# LED_board.net
KiCad netlist of a schematic drawn in EAGLE
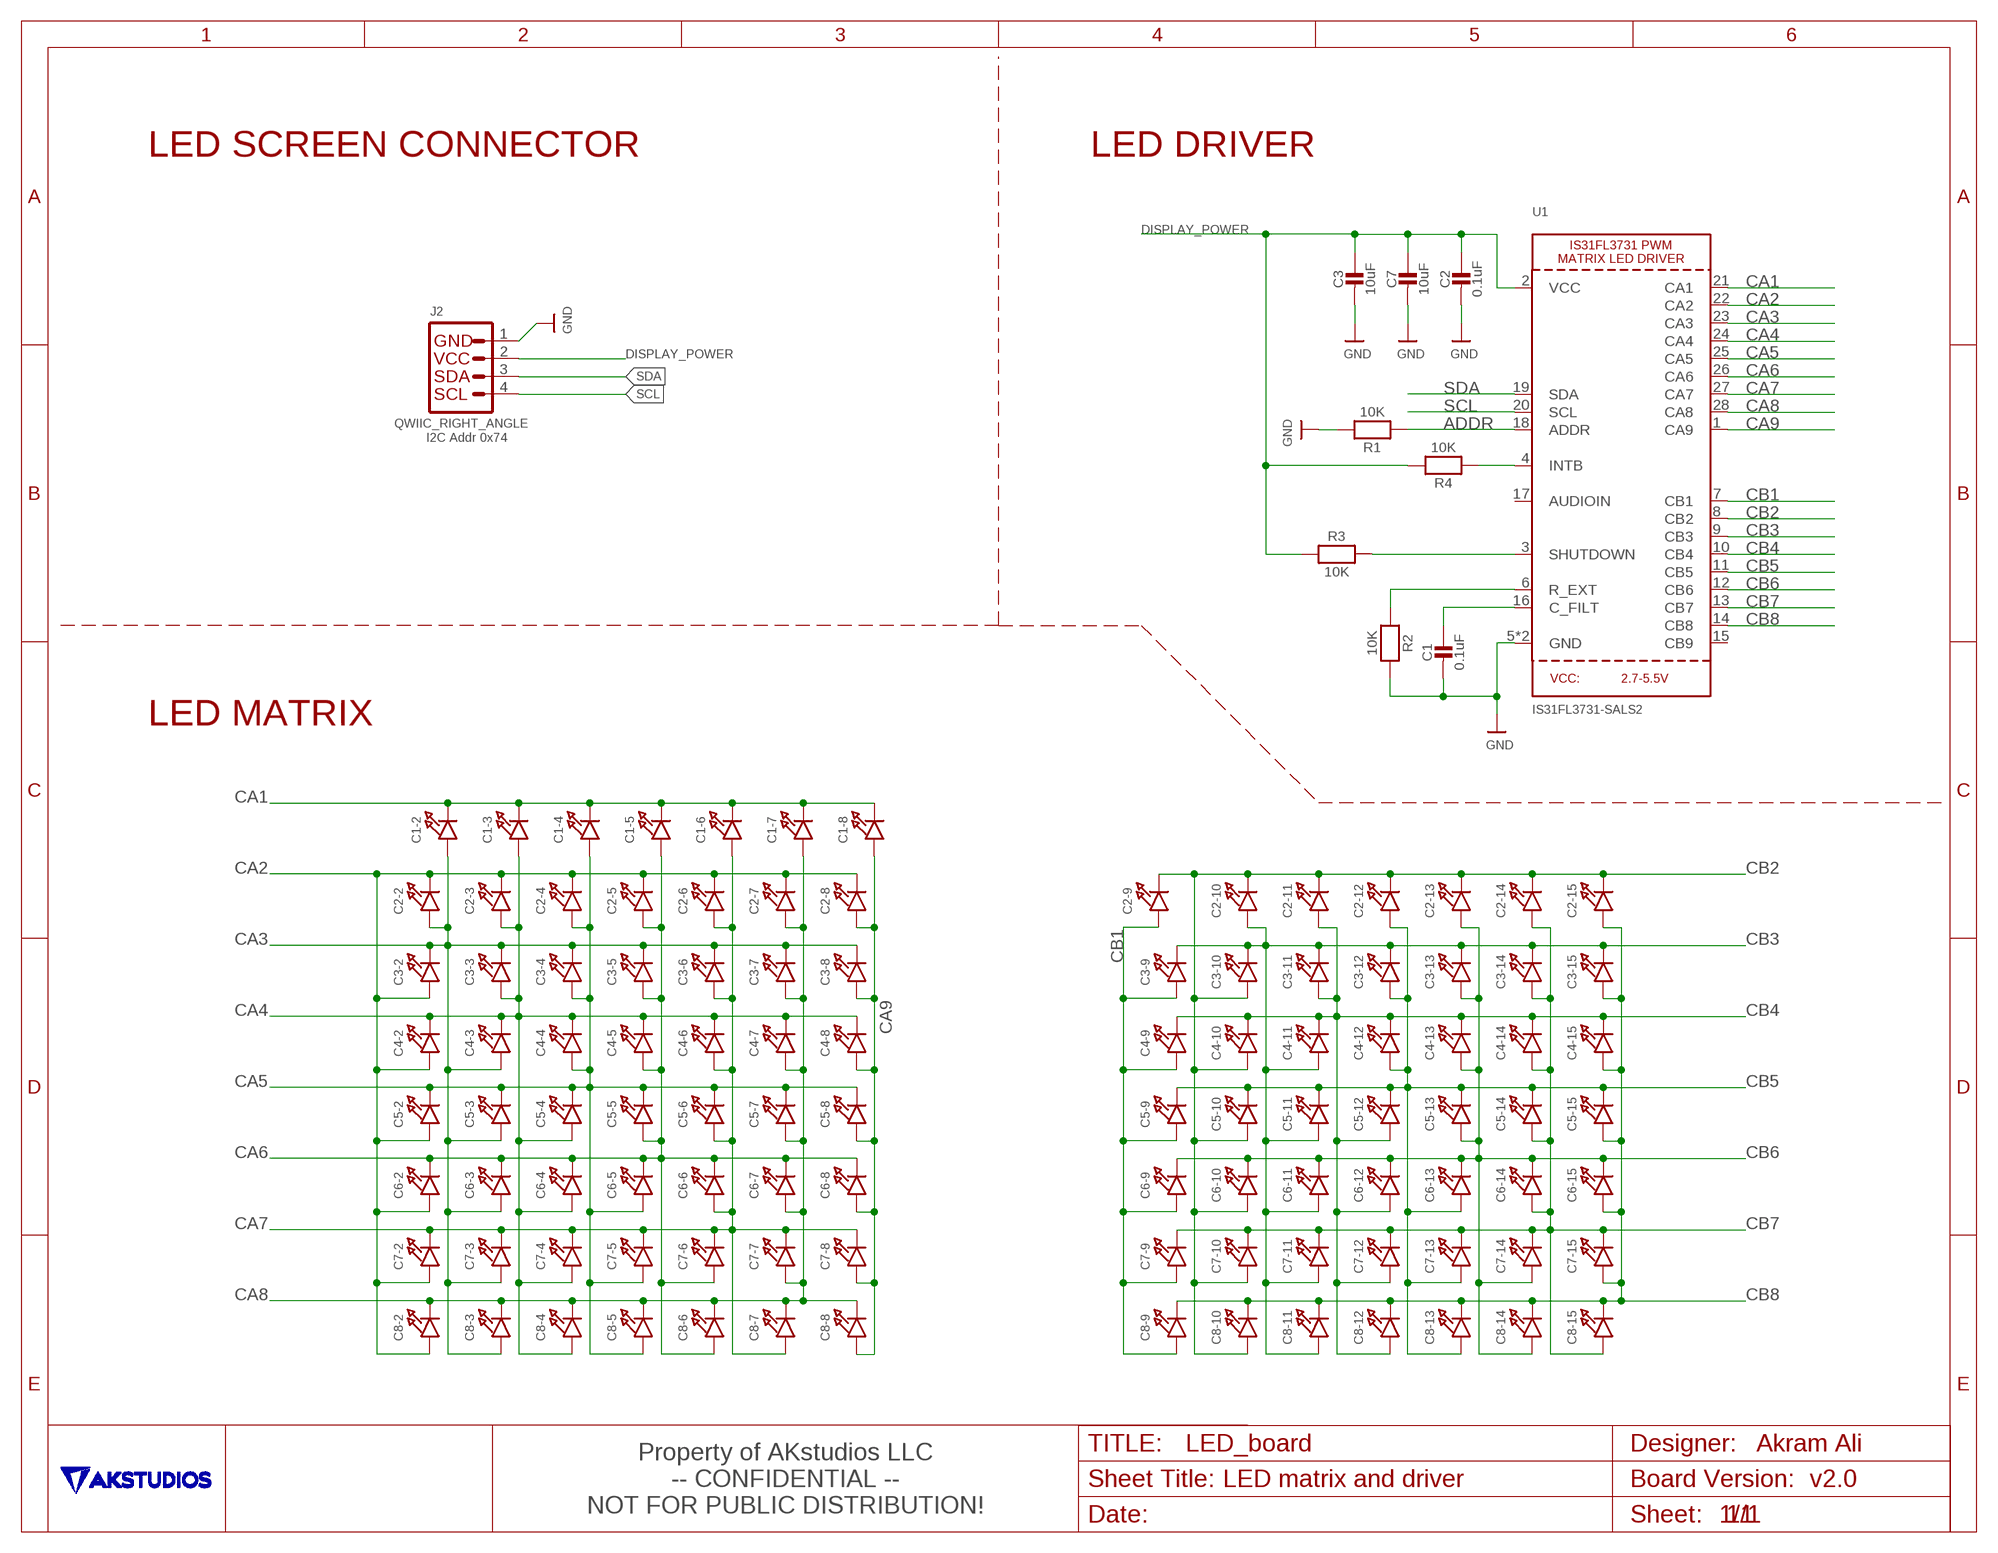
[diagram p0: schematic, sheet 1]

(export (version "E")
  (design (tool "Eeschema 10.0.6"))
  (components
    (comp (ref "C1")
      (value "0.1uF")
      (footprint "eagle-import:MICROBUILDER__0402MP")
      (fields (field (name "MPN") "GRM155R71C104KA88J"))
      (libsource (lib "eagle-import") (part "MICROBUILDER_CAP_CERAMIC_0402MP"))
    )
    (comp (ref "C1-2")
      (value "LED0603_NOOUTLINE")
      (footprint "eagle-import:CHIPLED_0603_NOOUTLINE")
      (libsource (lib "eagle-import") (part "LED0603_NOOUTLINE"))
    )
    (comp (ref "C1-3")
      (value "LED0603_NOOUTLINE")
      (footprint "eagle-import:CHIPLED_0603_NOOUTLINE")
      (libsource (lib "eagle-import") (part "LED0603_NOOUTLINE"))
    )
    (comp (ref "C1-4")
      (value "LED0603_NOOUTLINE")
      (footprint "eagle-import:CHIPLED_0603_NOOUTLINE")
      (libsource (lib "eagle-import") (part "LED0603_NOOUTLINE"))
    )
    (comp (ref "C1-5")
      (value "LED0603_NOOUTLINE")
      (footprint "eagle-import:CHIPLED_0603_NOOUTLINE")
      (libsource (lib "eagle-import") (part "LED0603_NOOUTLINE"))
    )
    (comp (ref "C1-6")
      (value "LED0603_NOOUTLINE")
      (footprint "eagle-import:CHIPLED_0603_NOOUTLINE")
      (libsource (lib "eagle-import") (part "LED0603_NOOUTLINE"))
    )
    (comp (ref "C1-7")
      (value "LED0603_NOOUTLINE")
      (footprint "eagle-import:CHIPLED_0603_NOOUTLINE")
      (libsource (lib "eagle-import") (part "LED0603_NOOUTLINE"))
    )
    (comp (ref "C1-8")
      (value "LED0603_NOOUTLINE")
      (footprint "eagle-import:CHIPLED_0603_NOOUTLINE")
      (libsource (lib "eagle-import") (part "LED0603_NOOUTLINE"))
    )
    (comp (ref "C2")
      (value "0.1uF")
      (footprint "eagle-import:MICROBUILDER__0402MP")
      (fields (field (name "MPN") "GRM155R71C104KA88J"))
      (libsource (lib "eagle-import") (part "MICROBUILDER_CAP_CERAMIC_0402MP"))
    )
    (comp (ref "C2-2")
      (value "LED0603_NOOUTLINE")
      (footprint "eagle-import:CHIPLED_0603_NOOUTLINE")
      (libsource (lib "eagle-import") (part "LED0603_NOOUTLINE"))
    )
    (comp (ref "C2-3")
      (value "LED0603_NOOUTLINE")
      (footprint "eagle-import:CHIPLED_0603_NOOUTLINE")
      (libsource (lib "eagle-import") (part "LED0603_NOOUTLINE"))
    )
    (comp (ref "C2-4")
      (value "LED0603_NOOUTLINE")
      (footprint "eagle-import:CHIPLED_0603_NOOUTLINE")
      (libsource (lib "eagle-import") (part "LED0603_NOOUTLINE"))
    )
    (comp (ref "C2-5")
      (value "LED0603_NOOUTLINE")
      (footprint "eagle-import:CHIPLED_0603_NOOUTLINE")
      (libsource (lib "eagle-import") (part "LED0603_NOOUTLINE"))
    )
    (comp (ref "C2-6")
      (value "LED0603_NOOUTLINE")
      (footprint "eagle-import:CHIPLED_0603_NOOUTLINE")
      (libsource (lib "eagle-import") (part "LED0603_NOOUTLINE"))
    )
    (comp (ref "C2-7")
      (value "LED0603_NOOUTLINE")
      (footprint "eagle-import:CHIPLED_0603_NOOUTLINE")
      (libsource (lib "eagle-import") (part "LED0603_NOOUTLINE"))
    )
    (comp (ref "C2-8")
      (value "LED0603_NOOUTLINE")
      (footprint "eagle-import:CHIPLED_0603_NOOUTLINE")
      (libsource (lib "eagle-import") (part "LED0603_NOOUTLINE"))
    )
    (comp (ref "C2-9")
      (value "LED0603_NOOUTLINE")
      (footprint "eagle-import:CHIPLED_0603_NOOUTLINE")
      (libsource (lib "eagle-import") (part "LED0603_NOOUTLINE"))
    )
    (comp (ref "C2-10")
      (value "LED0603_NOOUTLINE")
      (footprint "eagle-import:CHIPLED_0603_NOOUTLINE")
      (libsource (lib "eagle-import") (part "LED0603_NOOUTLINE"))
    )
    (comp (ref "C2-11")
      (value "LED0603_NOOUTLINE")
      (footprint "eagle-import:CHIPLED_0603_NOOUTLINE")
      (libsource (lib "eagle-import") (part "LED0603_NOOUTLINE"))
    )
    (comp (ref "C2-12")
      (value "LED0603_NOOUTLINE")
      (footprint "eagle-import:CHIPLED_0603_NOOUTLINE")
      (libsource (lib "eagle-import") (part "LED0603_NOOUTLINE"))
    )
    (comp (ref "C2-13")
      (value "LED0603_NOOUTLINE")
      (footprint "eagle-import:CHIPLED_0603_NOOUTLINE")
      (libsource (lib "eagle-import") (part "LED0603_NOOUTLINE"))
    )
    (comp (ref "C2-14")
      (value "LED0603_NOOUTLINE")
      (footprint "eagle-import:CHIPLED_0603_NOOUTLINE")
      (libsource (lib "eagle-import") (part "LED0603_NOOUTLINE"))
    )
    (comp (ref "C2-15")
      (value "LED0603_NOOUTLINE")
      (footprint "eagle-import:CHIPLED_0603_NOOUTLINE")
      (libsource (lib "eagle-import") (part "LED0603_NOOUTLINE"))
    )
    (comp (ref "C3")
      (value "10uF")
      (footprint "eagle-import:MICROBUILDER__0402MP")
      (fields (field (name "MPN") "GRM155R71C104KA88J"))
      (libsource (lib "eagle-import") (part "MICROBUILDER_CAP_CERAMIC_0402MP"))
    )
    (comp (ref "C3-2")
      (value "LED0603_NOOUTLINE")
      (footprint "eagle-import:CHIPLED_0603_NOOUTLINE")
      (libsource (lib "eagle-import") (part "LED0603_NOOUTLINE"))
    )
    (comp (ref "C3-3")
      (value "LED0603_NOOUTLINE")
      (footprint "eagle-import:CHIPLED_0603_NOOUTLINE")
      (libsource (lib "eagle-import") (part "LED0603_NOOUTLINE"))
    )
    (comp (ref "C3-4")
      (value "LED0603_NOOUTLINE")
      (footprint "eagle-import:CHIPLED_0603_NOOUTLINE")
      (libsource (lib "eagle-import") (part "LED0603_NOOUTLINE"))
    )
    (comp (ref "C3-5")
      (value "LED0603_NOOUTLINE")
      (footprint "eagle-import:CHIPLED_0603_NOOUTLINE")
      (libsource (lib "eagle-import") (part "LED0603_NOOUTLINE"))
    )
    (comp (ref "C3-6")
      (value "LED0603_NOOUTLINE")
      (footprint "eagle-import:CHIPLED_0603_NOOUTLINE")
      (libsource (lib "eagle-import") (part "LED0603_NOOUTLINE"))
    )
    (comp (ref "C3-7")
      (value "LED0603_NOOUTLINE")
      (footprint "eagle-import:CHIPLED_0603_NOOUTLINE")
      (libsource (lib "eagle-import") (part "LED0603_NOOUTLINE"))
    )
    (comp (ref "C3-8")
      (value "LED0603_NOOUTLINE")
      (footprint "eagle-import:CHIPLED_0603_NOOUTLINE")
      (libsource (lib "eagle-import") (part "LED0603_NOOUTLINE"))
    )
    (comp (ref "C3-9")
      (value "LED0603_NOOUTLINE")
      (footprint "eagle-import:CHIPLED_0603_NOOUTLINE")
      (libsource (lib "eagle-import") (part "LED0603_NOOUTLINE"))
    )
    (comp (ref "C3-10")
      (value "LED0603_NOOUTLINE")
      (footprint "eagle-import:CHIPLED_0603_NOOUTLINE")
      (libsource (lib "eagle-import") (part "LED0603_NOOUTLINE"))
    )
    (comp (ref "C3-11")
      (value "LED0603_NOOUTLINE")
      (footprint "eagle-import:CHIPLED_0603_NOOUTLINE")
      (libsource (lib "eagle-import") (part "LED0603_NOOUTLINE"))
    )
    (comp (ref "C3-12")
      (value "LED0603_NOOUTLINE")
      (footprint "eagle-import:CHIPLED_0603_NOOUTLINE")
      (libsource (lib "eagle-import") (part "LED0603_NOOUTLINE"))
    )
    (comp (ref "C3-13")
      (value "LED0603_NOOUTLINE")
      (footprint "eagle-import:CHIPLED_0603_NOOUTLINE")
      (libsource (lib "eagle-import") (part "LED0603_NOOUTLINE"))
    )
    (comp (ref "C3-14")
      (value "LED0603_NOOUTLINE")
      (footprint "eagle-import:CHIPLED_0603_NOOUTLINE")
      (libsource (lib "eagle-import") (part "LED0603_NOOUTLINE"))
    )
    (comp (ref "C3-15")
      (value "LED0603_NOOUTLINE")
      (footprint "eagle-import:CHIPLED_0603_NOOUTLINE")
      (libsource (lib "eagle-import") (part "LED0603_NOOUTLINE"))
    )
    (comp (ref "C4-2")
      (value "LED0603_NOOUTLINE")
      (footprint "eagle-import:CHIPLED_0603_NOOUTLINE")
      (libsource (lib "eagle-import") (part "LED0603_NOOUTLINE"))
    )
    (comp (ref "C4-3")
      (value "LED0603_NOOUTLINE")
      (footprint "eagle-import:CHIPLED_0603_NOOUTLINE")
      (libsource (lib "eagle-import") (part "LED0603_NOOUTLINE"))
    )
    (comp (ref "C4-4")
      (value "LED0603_NOOUTLINE")
      (footprint "eagle-import:CHIPLED_0603_NOOUTLINE")
      (libsource (lib "eagle-import") (part "LED0603_NOOUTLINE"))
    )
    (comp (ref "C4-5")
      (value "LED0603_NOOUTLINE")
      (footprint "eagle-import:CHIPLED_0603_NOOUTLINE")
      (libsource (lib "eagle-import") (part "LED0603_NOOUTLINE"))
    )
    (comp (ref "C4-6")
      (value "LED0603_NOOUTLINE")
      (footprint "eagle-import:CHIPLED_0603_NOOUTLINE")
      (libsource (lib "eagle-import") (part "LED0603_NOOUTLINE"))
    )
    (comp (ref "C4-7")
      (value "LED0603_NOOUTLINE")
      (footprint "eagle-import:CHIPLED_0603_NOOUTLINE")
      (libsource (lib "eagle-import") (part "LED0603_NOOUTLINE"))
    )
    (comp (ref "C4-8")
      (value "LED0603_NOOUTLINE")
      (footprint "eagle-import:CHIPLED_0603_NOOUTLINE")
      (libsource (lib "eagle-import") (part "LED0603_NOOUTLINE"))
    )
    (comp (ref "C4-9")
      (value "LED0603_NOOUTLINE")
      (footprint "eagle-import:CHIPLED_0603_NOOUTLINE")
      (libsource (lib "eagle-import") (part "LED0603_NOOUTLINE"))
    )
    (comp (ref "C4-10")
      (value "LED0603_NOOUTLINE")
      (footprint "eagle-import:CHIPLED_0603_NOOUTLINE")
      (libsource (lib "eagle-import") (part "LED0603_NOOUTLINE"))
    )
    (comp (ref "C4-11")
      (value "LED0603_NOOUTLINE")
      (footprint "eagle-import:CHIPLED_0603_NOOUTLINE")
      (libsource (lib "eagle-import") (part "LED0603_NOOUTLINE"))
    )
    (comp (ref "C4-12")
      (value "LED0603_NOOUTLINE")
      (footprint "eagle-import:CHIPLED_0603_NOOUTLINE")
      (libsource (lib "eagle-import") (part "LED0603_NOOUTLINE"))
    )
    (comp (ref "C4-13")
      (value "LED0603_NOOUTLINE")
      (footprint "eagle-import:CHIPLED_0603_NOOUTLINE")
      (libsource (lib "eagle-import") (part "LED0603_NOOUTLINE"))
    )
    (comp (ref "C4-14")
      (value "LED0603_NOOUTLINE")
      (footprint "eagle-import:CHIPLED_0603_NOOUTLINE")
      (libsource (lib "eagle-import") (part "LED0603_NOOUTLINE"))
    )
    (comp (ref "C4-15")
      (value "LED0603_NOOUTLINE")
      (footprint "eagle-import:CHIPLED_0603_NOOUTLINE")
      (libsource (lib "eagle-import") (part "LED0603_NOOUTLINE"))
    )
    (comp (ref "C5-2")
      (value "LED0603_NOOUTLINE")
      (footprint "eagle-import:CHIPLED_0603_NOOUTLINE")
      (libsource (lib "eagle-import") (part "LED0603_NOOUTLINE"))
    )
    (comp (ref "C5-3")
      (value "LED0603_NOOUTLINE")
      (footprint "eagle-import:CHIPLED_0603_NOOUTLINE")
      (libsource (lib "eagle-import") (part "LED0603_NOOUTLINE"))
    )
    (comp (ref "C5-4")
      (value "LED0603_NOOUTLINE")
      (footprint "eagle-import:CHIPLED_0603_NOOUTLINE")
      (libsource (lib "eagle-import") (part "LED0603_NOOUTLINE"))
    )
    (comp (ref "C5-5")
      (value "LED0603_NOOUTLINE")
      (footprint "eagle-import:CHIPLED_0603_NOOUTLINE")
      (libsource (lib "eagle-import") (part "LED0603_NOOUTLINE"))
    )
    (comp (ref "C5-6")
      (value "LED0603_NOOUTLINE")
      (footprint "eagle-import:CHIPLED_0603_NOOUTLINE")
      (libsource (lib "eagle-import") (part "LED0603_NOOUTLINE"))
    )
    (comp (ref "C5-7")
      (value "LED0603_NOOUTLINE")
      (footprint "eagle-import:CHIPLED_0603_NOOUTLINE")
      (libsource (lib "eagle-import") (part "LED0603_NOOUTLINE"))
    )
    (comp (ref "C5-8")
      (value "LED0603_NOOUTLINE")
      (footprint "eagle-import:CHIPLED_0603_NOOUTLINE")
      (libsource (lib "eagle-import") (part "LED0603_NOOUTLINE"))
    )
    (comp (ref "C5-9")
      (value "LED0603_NOOUTLINE")
      (footprint "eagle-import:CHIPLED_0603_NOOUTLINE")
      (libsource (lib "eagle-import") (part "LED0603_NOOUTLINE"))
    )
    (comp (ref "C5-10")
      (value "LED0603_NOOUTLINE")
      (footprint "eagle-import:CHIPLED_0603_NOOUTLINE")
      (libsource (lib "eagle-import") (part "LED0603_NOOUTLINE"))
    )
    (comp (ref "C5-11")
      (value "LED0603_NOOUTLINE")
      (footprint "eagle-import:CHIPLED_0603_NOOUTLINE")
      (libsource (lib "eagle-import") (part "LED0603_NOOUTLINE"))
    )
    (comp (ref "C5-12")
      (value "LED0603_NOOUTLINE")
      (footprint "eagle-import:CHIPLED_0603_NOOUTLINE")
      (libsource (lib "eagle-import") (part "LED0603_NOOUTLINE"))
    )
    (comp (ref "C5-13")
      (value "LED0603_NOOUTLINE")
      (footprint "eagle-import:CHIPLED_0603_NOOUTLINE")
      (libsource (lib "eagle-import") (part "LED0603_NOOUTLINE"))
    )
    (comp (ref "C5-14")
      (value "LED0603_NOOUTLINE")
      (footprint "eagle-import:CHIPLED_0603_NOOUTLINE")
      (libsource (lib "eagle-import") (part "LED0603_NOOUTLINE"))
    )
    (comp (ref "C5-15")
      (value "LED0603_NOOUTLINE")
      (footprint "eagle-import:CHIPLED_0603_NOOUTLINE")
      (libsource (lib "eagle-import") (part "LED0603_NOOUTLINE"))
    )
    (comp (ref "C6-2")
      (value "LED0603_NOOUTLINE")
      (footprint "eagle-import:CHIPLED_0603_NOOUTLINE")
      (libsource (lib "eagle-import") (part "LED0603_NOOUTLINE"))
    )
    (comp (ref "C6-3")
      (value "LED0603_NOOUTLINE")
      (footprint "eagle-import:CHIPLED_0603_NOOUTLINE")
      (libsource (lib "eagle-import") (part "LED0603_NOOUTLINE"))
    )
    (comp (ref "C6-4")
      (value "LED0603_NOOUTLINE")
      (footprint "eagle-import:CHIPLED_0603_NOOUTLINE")
      (libsource (lib "eagle-import") (part "LED0603_NOOUTLINE"))
    )
    (comp (ref "C6-5")
      (value "LED0603_NOOUTLINE")
      (footprint "eagle-import:CHIPLED_0603_NOOUTLINE")
      (libsource (lib "eagle-import") (part "LED0603_NOOUTLINE"))
    )
    (comp (ref "C6-6")
      (value "LED0603_NOOUTLINE")
      (footprint "eagle-import:CHIPLED_0603_NOOUTLINE")
      (libsource (lib "eagle-import") (part "LED0603_NOOUTLINE"))
    )
    (comp (ref "C6-7")
      (value "LED0603_NOOUTLINE")
      (footprint "eagle-import:CHIPLED_0603_NOOUTLINE")
      (libsource (lib "eagle-import") (part "LED0603_NOOUTLINE"))
    )
    (comp (ref "C6-8")
      (value "LED0603_NOOUTLINE")
      (footprint "eagle-import:CHIPLED_0603_NOOUTLINE")
      (libsource (lib "eagle-import") (part "LED0603_NOOUTLINE"))
    )
    (comp (ref "C6-9")
      (value "LED0603_NOOUTLINE")
      (footprint "eagle-import:CHIPLED_0603_NOOUTLINE")
      (libsource (lib "eagle-import") (part "LED0603_NOOUTLINE"))
    )
    (comp (ref "C6-10")
      (value "LED0603_NOOUTLINE")
      (footprint "eagle-import:CHIPLED_0603_NOOUTLINE")
      (libsource (lib "eagle-import") (part "LED0603_NOOUTLINE"))
    )
    (comp (ref "C6-11")
      (value "LED0603_NOOUTLINE")
      (footprint "eagle-import:CHIPLED_0603_NOOUTLINE")
      (libsource (lib "eagle-import") (part "LED0603_NOOUTLINE"))
    )
    (comp (ref "C6-12")
      (value "LED0603_NOOUTLINE")
      (footprint "eagle-import:CHIPLED_0603_NOOUTLINE")
      (libsource (lib "eagle-import") (part "LED0603_NOOUTLINE"))
    )
    (comp (ref "C6-13")
      (value "LED0603_NOOUTLINE")
      (footprint "eagle-import:CHIPLED_0603_NOOUTLINE")
      (libsource (lib "eagle-import") (part "LED0603_NOOUTLINE"))
    )
    (comp (ref "C6-14")
      (value "LED0603_NOOUTLINE")
      (footprint "eagle-import:CHIPLED_0603_NOOUTLINE")
      (libsource (lib "eagle-import") (part "LED0603_NOOUTLINE"))
    )
    (comp (ref "C6-15")
      (value "LED0603_NOOUTLINE")
      (footprint "eagle-import:CHIPLED_0603_NOOUTLINE")
      (libsource (lib "eagle-import") (part "LED0603_NOOUTLINE"))
    )
    (comp (ref "C7")
      (value "10uF")
      (footprint "eagle-import:MICROBUILDER__0402MP")
      (fields (field (name "MPN") "GRM155R71C104KA88J"))
      (libsource (lib "eagle-import") (part "MICROBUILDER_CAP_CERAMIC_0402MP"))
    )
    (comp (ref "C7-2")
      (value "LED0603_NOOUTLINE")
      (footprint "eagle-import:CHIPLED_0603_NOOUTLINE")
      (libsource (lib "eagle-import") (part "LED0603_NOOUTLINE"))
    )
    (comp (ref "C7-3")
      (value "LED0603_NOOUTLINE")
      (footprint "eagle-import:CHIPLED_0603_NOOUTLINE")
      (libsource (lib "eagle-import") (part "LED0603_NOOUTLINE"))
    )
    (comp (ref "C7-4")
      (value "LED0603_NOOUTLINE")
      (footprint "eagle-import:CHIPLED_0603_NOOUTLINE")
      (libsource (lib "eagle-import") (part "LED0603_NOOUTLINE"))
    )
    (comp (ref "C7-5")
      (value "LED0603_NOOUTLINE")
      (footprint "eagle-import:CHIPLED_0603_NOOUTLINE")
      (libsource (lib "eagle-import") (part "LED0603_NOOUTLINE"))
    )
    (comp (ref "C7-6")
      (value "LED0603_NOOUTLINE")
      (footprint "eagle-import:CHIPLED_0603_NOOUTLINE")
      (libsource (lib "eagle-import") (part "LED0603_NOOUTLINE"))
    )
    (comp (ref "C7-7")
      (value "LED0603_NOOUTLINE")
      (footprint "eagle-import:CHIPLED_0603_NOOUTLINE")
      (libsource (lib "eagle-import") (part "LED0603_NOOUTLINE"))
    )
    (comp (ref "C7-8")
      (value "LED0603_NOOUTLINE")
      (footprint "eagle-import:CHIPLED_0603_NOOUTLINE")
      (libsource (lib "eagle-import") (part "LED0603_NOOUTLINE"))
    )
    (comp (ref "C7-9")
      (value "LED0603_NOOUTLINE")
      (footprint "eagle-import:CHIPLED_0603_NOOUTLINE")
      (libsource (lib "eagle-import") (part "LED0603_NOOUTLINE"))
    )
    (comp (ref "C7-10")
      (value "LED0603_NOOUTLINE")
      (footprint "eagle-import:CHIPLED_0603_NOOUTLINE")
      (libsource (lib "eagle-import") (part "LED0603_NOOUTLINE"))
    )
    (comp (ref "C7-11")
      (value "LED0603_NOOUTLINE")
      (footprint "eagle-import:CHIPLED_0603_NOOUTLINE")
      (libsource (lib "eagle-import") (part "LED0603_NOOUTLINE"))
    )
    (comp (ref "C7-12")
      (value "LED0603_NOOUTLINE")
      (footprint "eagle-import:CHIPLED_0603_NOOUTLINE")
      (libsource (lib "eagle-import") (part "LED0603_NOOUTLINE"))
    )
    (comp (ref "C7-13")
      (value "LED0603_NOOUTLINE")
      (footprint "eagle-import:CHIPLED_0603_NOOUTLINE")
      (libsource (lib "eagle-import") (part "LED0603_NOOUTLINE"))
    )
    (comp (ref "C7-14")
      (value "LED0603_NOOUTLINE")
      (footprint "eagle-import:CHIPLED_0603_NOOUTLINE")
      (libsource (lib "eagle-import") (part "LED0603_NOOUTLINE"))
    )
    (comp (ref "C7-15")
      (value "LED0603_NOOUTLINE")
      (footprint "eagle-import:CHIPLED_0603_NOOUTLINE")
      (libsource (lib "eagle-import") (part "LED0603_NOOUTLINE"))
    )
    (comp (ref "C8-2")
      (value "LED0603_NOOUTLINE")
      (footprint "eagle-import:CHIPLED_0603_NOOUTLINE")
      (libsource (lib "eagle-import") (part "LED0603_NOOUTLINE"))
    )
    (comp (ref "C8-3")
      (value "LED0603_NOOUTLINE")
      (footprint "eagle-import:CHIPLED_0603_NOOUTLINE")
      (libsource (lib "eagle-import") (part "LED0603_NOOUTLINE"))
    )
    (comp (ref "C8-4")
      (value "LED0603_NOOUTLINE")
      (footprint "eagle-import:CHIPLED_0603_NOOUTLINE")
      (libsource (lib "eagle-import") (part "LED0603_NOOUTLINE"))
    )
    (comp (ref "C8-5")
      (value "LED0603_NOOUTLINE")
      (footprint "eagle-import:CHIPLED_0603_NOOUTLINE")
      (libsource (lib "eagle-import") (part "LED0603_NOOUTLINE"))
    )
    (comp (ref "C8-6")
      (value "LED0603_NOOUTLINE")
      (footprint "eagle-import:CHIPLED_0603_NOOUTLINE")
      (libsource (lib "eagle-import") (part "LED0603_NOOUTLINE"))
    )
    (comp (ref "C8-7")
      (value "LED0603_NOOUTLINE")
      (footprint "eagle-import:CHIPLED_0603_NOOUTLINE")
      (libsource (lib "eagle-import") (part "LED0603_NOOUTLINE"))
    )
    (comp (ref "C8-8")
      (value "LED0603_NOOUTLINE")
      (footprint "eagle-import:CHIPLED_0603_NOOUTLINE")
      (libsource (lib "eagle-import") (part "LED0603_NOOUTLINE"))
    )
    (comp (ref "C8-9")
      (value "LED0603_NOOUTLINE")
      (footprint "eagle-import:CHIPLED_0603_NOOUTLINE")
      (libsource (lib "eagle-import") (part "LED0603_NOOUTLINE"))
    )
    (comp (ref "C8-10")
      (value "LED0603_NOOUTLINE")
      (footprint "eagle-import:CHIPLED_0603_NOOUTLINE")
      (libsource (lib "eagle-import") (part "LED0603_NOOUTLINE"))
    )
    (comp (ref "C8-11")
      (value "LED0603_NOOUTLINE")
      (footprint "eagle-import:CHIPLED_0603_NOOUTLINE")
      (libsource (lib "eagle-import") (part "LED0603_NOOUTLINE"))
    )
    (comp (ref "C8-12")
      (value "LED0603_NOOUTLINE")
      (footprint "eagle-import:CHIPLED_0603_NOOUTLINE")
      (libsource (lib "eagle-import") (part "LED0603_NOOUTLINE"))
    )
    (comp (ref "C8-13")
      (value "LED0603_NOOUTLINE")
      (footprint "eagle-import:CHIPLED_0603_NOOUTLINE")
      (libsource (lib "eagle-import") (part "LED0603_NOOUTLINE"))
    )
    (comp (ref "C8-14")
      (value "LED0603_NOOUTLINE")
      (footprint "eagle-import:CHIPLED_0603_NOOUTLINE")
      (libsource (lib "eagle-import") (part "LED0603_NOOUTLINE"))
    )
    (comp (ref "C8-15")
      (value "LED0603_NOOUTLINE")
      (footprint "eagle-import:CHIPLED_0603_NOOUTLINE")
      (libsource (lib "eagle-import") (part "LED0603_NOOUTLINE"))
    )
    (comp (ref "J2")
      (value "QWIIC_RIGHT_ANGLE")
      (footprint "eagle-import:JST04_1MM_RA")
      (fields (field (name "MPN") "SM04B-SRSS-TB(LF)(SN)"))
      (libsource (lib "eagle-import") (part "QWIIC_CONNECTORJS-1MM"))
    )
    (comp (ref "R1")
      (value "10K")
      (footprint "eagle-import:MICROBUILDER__0402MP")
      (fields (field (name "MPN") "RC0402FR-7W10KL"))
      (libsource (lib "eagle-import") (part "MICROBUILDER_RESISTOR_0402MP"))
    )
    (comp (ref "R2")
      (value "10K")
      (footprint "eagle-import:MICROBUILDER__0402MP")
      (fields (field (name "MPN") "RC0402FR-7W10KL"))
      (libsource (lib "eagle-import") (part "MICROBUILDER_RESISTOR_0402MP"))
    )
    (comp (ref "R3")
      (value "10K")
      (footprint "eagle-import:MICROBUILDER__0402MP")
      (fields (field (name "MPN") "RC0402FR-7W10KL"))
      (libsource (lib "eagle-import") (part "MICROBUILDER_RESISTOR_0402MP"))
    )
    (comp (ref "R4")
      (value "10K")
      (footprint "eagle-import:MICROBUILDER__0402MP")
      (fields (field (name "MPN") "RC0402FR-7W10KL"))
      (libsource (lib "eagle-import") (part "MICROBUILDER_RESISTOR_0402MP"))
    )
    (comp (ref "U1")
      (value "IS31FL3731-SALS2")
      (footprint "eagle-import:QFN28_4MM_0.4MM")
      (libsource (lib "eagle-import") (part "IS31FL3731QFN"))
    )
  )
  (nets
    (net (code "1") (name "/ADDR") (class "Default")
      (node (ref "R1") (pin "1") (pinfunction "1_1") (pintype "passive"))
      (node (ref "U1") (pin "18") (pinfunction "ADDR_18") (pintype "bidirectional"))
    )
    (net (code "2") (name "/CA1") (class "Default")
      (node (ref "C1-2") (pin "C") (pinfunction "C_C") (pintype "passive"))
      (node (ref "C1-3") (pin "C") (pinfunction "C_C") (pintype "passive"))
      (node (ref "C1-4") (pin "C") (pinfunction "C_C") (pintype "passive"))
      (node (ref "C1-5") (pin "C") (pinfunction "C_C") (pintype "passive"))
      (node (ref "C1-6") (pin "C") (pinfunction "C_C") (pintype "passive"))
      (node (ref "C1-7") (pin "C") (pinfunction "C_C") (pintype "passive"))
      (node (ref "C1-8") (pin "C") (pinfunction "C_C") (pintype "passive"))
      (node (ref "U1") (pin "21") (pinfunction "CA1_21") (pintype "bidirectional"))
    )
    (net (code "3") (name "/CA2") (class "Default")
      (node (ref "C2-2") (pin "C") (pinfunction "C_C") (pintype "passive"))
      (node (ref "C2-3") (pin "C") (pinfunction "C_C") (pintype "passive"))
      (node (ref "C2-4") (pin "C") (pinfunction "C_C") (pintype "passive"))
      (node (ref "C2-5") (pin "C") (pinfunction "C_C") (pintype "passive"))
      (node (ref "C2-6") (pin "C") (pinfunction "C_C") (pintype "passive"))
      (node (ref "C2-7") (pin "C") (pinfunction "C_C") (pintype "passive"))
      (node (ref "C2-8") (pin "C") (pinfunction "C_C") (pintype "passive"))
      (node (ref "C3-2") (pin "A") (pinfunction "A_A") (pintype "passive"))
      (node (ref "C4-2") (pin "A") (pinfunction "A_A") (pintype "passive"))
      (node (ref "C5-2") (pin "A") (pinfunction "A_A") (pintype "passive"))
      (node (ref "C6-2") (pin "A") (pinfunction "A_A") (pintype "passive"))
      (node (ref "C7-2") (pin "A") (pinfunction "A_A") (pintype "passive"))
      (node (ref "C8-2") (pin "A") (pinfunction "A_A") (pintype "passive"))
      (node (ref "U1") (pin "22") (pinfunction "CA2_22") (pintype "bidirectional"))
    )
    (net (code "4") (name "/CA3") (class "Default")
      (node (ref "C1-2") (pin "A") (pinfunction "A_A") (pintype "passive"))
      (node (ref "C2-2") (pin "A") (pinfunction "A_A") (pintype "passive"))
      (node (ref "C3-2") (pin "C") (pinfunction "C_C") (pintype "passive"))
      (node (ref "C3-3") (pin "C") (pinfunction "C_C") (pintype "passive"))
      (node (ref "C3-4") (pin "C") (pinfunction "C_C") (pintype "passive"))
      (node (ref "C3-5") (pin "C") (pinfunction "C_C") (pintype "passive"))
      (node (ref "C3-6") (pin "C") (pinfunction "C_C") (pintype "passive"))
      (node (ref "C3-7") (pin "C") (pinfunction "C_C") (pintype "passive"))
      (node (ref "C3-8") (pin "C") (pinfunction "C_C") (pintype "passive"))
      (node (ref "C4-3") (pin "A") (pinfunction "A_A") (pintype "passive"))
      (node (ref "C5-3") (pin "A") (pinfunction "A_A") (pintype "passive"))
      (node (ref "C6-3") (pin "A") (pinfunction "A_A") (pintype "passive"))
      (node (ref "C7-3") (pin "A") (pinfunction "A_A") (pintype "passive"))
      (node (ref "C8-3") (pin "A") (pinfunction "A_A") (pintype "passive"))
      (node (ref "U1") (pin "23") (pinfunction "CA3_23") (pintype "bidirectional"))
    )
    (net (code "5") (name "/CA4") (class "Default")
      (node (ref "C1-3") (pin "A") (pinfunction "A_A") (pintype "passive"))
      (node (ref "C2-3") (pin "A") (pinfunction "A_A") (pintype "passive"))
      (node (ref "C3-3") (pin "A") (pinfunction "A_A") (pintype "passive"))
      (node (ref "C4-2") (pin "C") (pinfunction "C_C") (pintype "passive"))
      (node (ref "C4-3") (pin "C") (pinfunction "C_C") (pintype "passive"))
      (node (ref "C4-4") (pin "C") (pinfunction "C_C") (pintype "passive"))
      (node (ref "C4-5") (pin "C") (pinfunction "C_C") (pintype "passive"))
      (node (ref "C4-6") (pin "C") (pinfunction "C_C") (pintype "passive"))
      (node (ref "C4-7") (pin "C") (pinfunction "C_C") (pintype "passive"))
      (node (ref "C4-8") (pin "C") (pinfunction "C_C") (pintype "passive"))
      (node (ref "C5-4") (pin "A") (pinfunction "A_A") (pintype "passive"))
      (node (ref "C6-4") (pin "A") (pinfunction "A_A") (pintype "passive"))
      (node (ref "C7-4") (pin "A") (pinfunction "A_A") (pintype "passive"))
      (node (ref "C8-4") (pin "A") (pinfunction "A_A") (pintype "passive"))
      (node (ref "U1") (pin "24") (pinfunction "CA4_24") (pintype "bidirectional"))
    )
    (net (code "6") (name "/CA5") (class "Default")
      (node (ref "C1-4") (pin "A") (pinfunction "A_A") (pintype "passive"))
      (node (ref "C2-4") (pin "A") (pinfunction "A_A") (pintype "passive"))
      (node (ref "C3-4") (pin "A") (pinfunction "A_A") (pintype "passive"))
      (node (ref "C4-4") (pin "A") (pinfunction "A_A") (pintype "passive"))
      (node (ref "C5-2") (pin "C") (pinfunction "C_C") (pintype "passive"))
      (node (ref "C5-3") (pin "C") (pinfunction "C_C") (pintype "passive"))
      (node (ref "C5-4") (pin "C") (pinfunction "C_C") (pintype "passive"))
      (node (ref "C5-5") (pin "C") (pinfunction "C_C") (pintype "passive"))
      (node (ref "C5-6") (pin "C") (pinfunction "C_C") (pintype "passive"))
      (node (ref "C5-7") (pin "C") (pinfunction "C_C") (pintype "passive"))
      (node (ref "C5-8") (pin "C") (pinfunction "C_C") (pintype "passive"))
      (node (ref "C6-5") (pin "A") (pinfunction "A_A") (pintype "passive"))
      (node (ref "C7-5") (pin "A") (pinfunction "A_A") (pintype "passive"))
      (node (ref "C8-5") (pin "A") (pinfunction "A_A") (pintype "passive"))
      (node (ref "U1") (pin "25") (pinfunction "CA5_25") (pintype "bidirectional"))
    )
    (net (code "7") (name "/CA6") (class "Default")
      (node (ref "C1-5") (pin "A") (pinfunction "A_A") (pintype "passive"))
      (node (ref "C2-5") (pin "A") (pinfunction "A_A") (pintype "passive"))
      (node (ref "C3-5") (pin "A") (pinfunction "A_A") (pintype "passive"))
      (node (ref "C4-5") (pin "A") (pinfunction "A_A") (pintype "passive"))
      (node (ref "C5-5") (pin "A") (pinfunction "A_A") (pintype "passive"))
      (node (ref "C6-2") (pin "C") (pinfunction "C_C") (pintype "passive"))
      (node (ref "C6-3") (pin "C") (pinfunction "C_C") (pintype "passive"))
      (node (ref "C6-4") (pin "C") (pinfunction "C_C") (pintype "passive"))
      (node (ref "C6-5") (pin "C") (pinfunction "C_C") (pintype "passive"))
      (node (ref "C6-6") (pin "C") (pinfunction "C_C") (pintype "passive"))
      (node (ref "C6-7") (pin "C") (pinfunction "C_C") (pintype "passive"))
      (node (ref "C6-8") (pin "C") (pinfunction "C_C") (pintype "passive"))
      (node (ref "C7-6") (pin "A") (pinfunction "A_A") (pintype "passive"))
      (node (ref "C8-6") (pin "A") (pinfunction "A_A") (pintype "passive"))
      (node (ref "U1") (pin "26") (pinfunction "CA6_26") (pintype "bidirectional"))
    )
    (net (code "8") (name "/CA7") (class "Default")
      (node (ref "C1-6") (pin "A") (pinfunction "A_A") (pintype "passive"))
      (node (ref "C2-6") (pin "A") (pinfunction "A_A") (pintype "passive"))
      (node (ref "C3-6") (pin "A") (pinfunction "A_A") (pintype "passive"))
      (node (ref "C4-6") (pin "A") (pinfunction "A_A") (pintype "passive"))
      (node (ref "C5-6") (pin "A") (pinfunction "A_A") (pintype "passive"))
      (node (ref "C6-6") (pin "A") (pinfunction "A_A") (pintype "passive"))
      (node (ref "C7-2") (pin "C") (pinfunction "C_C") (pintype "passive"))
      (node (ref "C7-3") (pin "C") (pinfunction "C_C") (pintype "passive"))
      (node (ref "C7-4") (pin "C") (pinfunction "C_C") (pintype "passive"))
      (node (ref "C7-5") (pin "C") (pinfunction "C_C") (pintype "passive"))
      (node (ref "C7-6") (pin "C") (pinfunction "C_C") (pintype "passive"))
      (node (ref "C7-7") (pin "C") (pinfunction "C_C") (pintype "passive"))
      (node (ref "C7-8") (pin "C") (pinfunction "C_C") (pintype "passive"))
      (node (ref "C8-7") (pin "A") (pinfunction "A_A") (pintype "passive"))
      (node (ref "U1") (pin "27") (pinfunction "CA7_27") (pintype "bidirectional"))
    )
    (net (code "9") (name "/CA8") (class "Default")
      (node (ref "C1-7") (pin "A") (pinfunction "A_A") (pintype "passive"))
      (node (ref "C2-7") (pin "A") (pinfunction "A_A") (pintype "passive"))
      (node (ref "C3-7") (pin "A") (pinfunction "A_A") (pintype "passive"))
      (node (ref "C4-7") (pin "A") (pinfunction "A_A") (pintype "passive"))
      (node (ref "C5-7") (pin "A") (pinfunction "A_A") (pintype "passive"))
      (node (ref "C6-7") (pin "A") (pinfunction "A_A") (pintype "passive"))
      (node (ref "C7-7") (pin "A") (pinfunction "A_A") (pintype "passive"))
      (node (ref "C8-2") (pin "C") (pinfunction "C_C") (pintype "passive"))
      (node (ref "C8-3") (pin "C") (pinfunction "C_C") (pintype "passive"))
      (node (ref "C8-4") (pin "C") (pinfunction "C_C") (pintype "passive"))
      (node (ref "C8-5") (pin "C") (pinfunction "C_C") (pintype "passive"))
      (node (ref "C8-6") (pin "C") (pinfunction "C_C") (pintype "passive"))
      (node (ref "C8-7") (pin "C") (pinfunction "C_C") (pintype "passive"))
      (node (ref "C8-8") (pin "C") (pinfunction "C_C") (pintype "passive"))
      (node (ref "U1") (pin "28") (pinfunction "CA8_28") (pintype "bidirectional"))
    )
    (net (code "10") (name "/CA9") (class "Default")
      (node (ref "C1-8") (pin "A") (pinfunction "A_A") (pintype "passive"))
      (node (ref "C2-8") (pin "A") (pinfunction "A_A") (pintype "passive"))
      (node (ref "C3-8") (pin "A") (pinfunction "A_A") (pintype "passive"))
      (node (ref "C4-8") (pin "A") (pinfunction "A_A") (pintype "passive"))
      (node (ref "C5-8") (pin "A") (pinfunction "A_A") (pintype "passive"))
      (node (ref "C6-8") (pin "A") (pinfunction "A_A") (pintype "passive"))
      (node (ref "C7-8") (pin "A") (pinfunction "A_A") (pintype "passive"))
      (node (ref "C8-8") (pin "A") (pinfunction "A_A") (pintype "passive"))
      (node (ref "U1") (pin "1") (pinfunction "CA9_1") (pintype "bidirectional"))
    )
    (net (code "11") (name "/CB1") (class "Default")
      (node (ref "C2-9") (pin "A") (pinfunction "A_A") (pintype "passive"))
      (node (ref "C3-9") (pin "A") (pinfunction "A_A") (pintype "passive"))
      (node (ref "C4-9") (pin "A") (pinfunction "A_A") (pintype "passive"))
      (node (ref "C5-9") (pin "A") (pinfunction "A_A") (pintype "passive"))
      (node (ref "C6-9") (pin "A") (pinfunction "A_A") (pintype "passive"))
      (node (ref "C7-9") (pin "A") (pinfunction "A_A") (pintype "passive"))
      (node (ref "C8-9") (pin "A") (pinfunction "A_A") (pintype "passive"))
      (node (ref "U1") (pin "7") (pinfunction "CB1_7") (pintype "bidirectional"))
    )
    (net (code "12") (name "/CB2") (class "Default")
      (node (ref "C2-10") (pin "C") (pinfunction "C_C") (pintype "passive"))
      (node (ref "C2-11") (pin "C") (pinfunction "C_C") (pintype "passive"))
      (node (ref "C2-12") (pin "C") (pinfunction "C_C") (pintype "passive"))
      (node (ref "C2-13") (pin "C") (pinfunction "C_C") (pintype "passive"))
      (node (ref "C2-14") (pin "C") (pinfunction "C_C") (pintype "passive"))
      (node (ref "C2-15") (pin "C") (pinfunction "C_C") (pintype "passive"))
      (node (ref "C2-9") (pin "C") (pinfunction "C_C") (pintype "passive"))
      (node (ref "C3-10") (pin "A") (pinfunction "A_A") (pintype "passive"))
      (node (ref "C4-10") (pin "A") (pinfunction "A_A") (pintype "passive"))
      (node (ref "C5-10") (pin "A") (pinfunction "A_A") (pintype "passive"))
      (node (ref "C6-10") (pin "A") (pinfunction "A_A") (pintype "passive"))
      (node (ref "C7-10") (pin "A") (pinfunction "A_A") (pintype "passive"))
      (node (ref "C8-10") (pin "A") (pinfunction "A_A") (pintype "passive"))
      (node (ref "U1") (pin "8") (pinfunction "CB2_8") (pintype "bidirectional"))
    )
    (net (code "13") (name "/CB3") (class "Default")
      (node (ref "C2-10") (pin "A") (pinfunction "A_A") (pintype "passive"))
      (node (ref "C3-10") (pin "C") (pinfunction "C_C") (pintype "passive"))
      (node (ref "C3-11") (pin "C") (pinfunction "C_C") (pintype "passive"))
      (node (ref "C3-12") (pin "C") (pinfunction "C_C") (pintype "passive"))
      (node (ref "C3-13") (pin "C") (pinfunction "C_C") (pintype "passive"))
      (node (ref "C3-14") (pin "C") (pinfunction "C_C") (pintype "passive"))
      (node (ref "C3-15") (pin "C") (pinfunction "C_C") (pintype "passive"))
      (node (ref "C3-9") (pin "C") (pinfunction "C_C") (pintype "passive"))
      (node (ref "C4-11") (pin "A") (pinfunction "A_A") (pintype "passive"))
      (node (ref "C5-11") (pin "A") (pinfunction "A_A") (pintype "passive"))
      (node (ref "C6-11") (pin "A") (pinfunction "A_A") (pintype "passive"))
      (node (ref "C7-11") (pin "A") (pinfunction "A_A") (pintype "passive"))
      (node (ref "C8-11") (pin "A") (pinfunction "A_A") (pintype "passive"))
      (node (ref "U1") (pin "9") (pinfunction "CB3_9") (pintype "bidirectional"))
    )
    (net (code "14") (name "/CB4") (class "Default")
      (node (ref "C2-11") (pin "A") (pinfunction "A_A") (pintype "passive"))
      (node (ref "C3-11") (pin "A") (pinfunction "A_A") (pintype "passive"))
      (node (ref "C4-10") (pin "C") (pinfunction "C_C") (pintype "passive"))
      (node (ref "C4-11") (pin "C") (pinfunction "C_C") (pintype "passive"))
      (node (ref "C4-12") (pin "C") (pinfunction "C_C") (pintype "passive"))
      (node (ref "C4-13") (pin "C") (pinfunction "C_C") (pintype "passive"))
      (node (ref "C4-14") (pin "C") (pinfunction "C_C") (pintype "passive"))
      (node (ref "C4-15") (pin "C") (pinfunction "C_C") (pintype "passive"))
      (node (ref "C4-9") (pin "C") (pinfunction "C_C") (pintype "passive"))
      (node (ref "C5-12") (pin "A") (pinfunction "A_A") (pintype "passive"))
      (node (ref "C6-12") (pin "A") (pinfunction "A_A") (pintype "passive"))
      (node (ref "C7-12") (pin "A") (pinfunction "A_A") (pintype "passive"))
      (node (ref "C8-12") (pin "A") (pinfunction "A_A") (pintype "passive"))
      (node (ref "U1") (pin "10") (pinfunction "CB4_10") (pintype "bidirectional"))
    )
    (net (code "15") (name "/CB5") (class "Default")
      (node (ref "C2-12") (pin "A") (pinfunction "A_A") (pintype "passive"))
      (node (ref "C3-12") (pin "A") (pinfunction "A_A") (pintype "passive"))
      (node (ref "C4-12") (pin "A") (pinfunction "A_A") (pintype "passive"))
      (node (ref "C5-10") (pin "C") (pinfunction "C_C") (pintype "passive"))
      (node (ref "C5-11") (pin "C") (pinfunction "C_C") (pintype "passive"))
      (node (ref "C5-12") (pin "C") (pinfunction "C_C") (pintype "passive"))
      (node (ref "C5-13") (pin "C") (pinfunction "C_C") (pintype "passive"))
      (node (ref "C5-14") (pin "C") (pinfunction "C_C") (pintype "passive"))
      (node (ref "C5-15") (pin "C") (pinfunction "C_C") (pintype "passive"))
      (node (ref "C5-9") (pin "C") (pinfunction "C_C") (pintype "passive"))
      (node (ref "C6-13") (pin "A") (pinfunction "A_A") (pintype "passive"))
      (node (ref "C7-13") (pin "A") (pinfunction "A_A") (pintype "passive"))
      (node (ref "C8-13") (pin "A") (pinfunction "A_A") (pintype "passive"))
      (node (ref "U1") (pin "11") (pinfunction "CB5_11") (pintype "bidirectional"))
    )
    (net (code "16") (name "/CB6") (class "Default")
      (node (ref "C2-13") (pin "A") (pinfunction "A_A") (pintype "passive"))
      (node (ref "C3-13") (pin "A") (pinfunction "A_A") (pintype "passive"))
      (node (ref "C4-13") (pin "A") (pinfunction "A_A") (pintype "passive"))
      (node (ref "C5-13") (pin "A") (pinfunction "A_A") (pintype "passive"))
      (node (ref "C6-10") (pin "C") (pinfunction "C_C") (pintype "passive"))
      (node (ref "C6-11") (pin "C") (pinfunction "C_C") (pintype "passive"))
      (node (ref "C6-12") (pin "C") (pinfunction "C_C") (pintype "passive"))
      (node (ref "C6-13") (pin "C") (pinfunction "C_C") (pintype "passive"))
      (node (ref "C6-14") (pin "C") (pinfunction "C_C") (pintype "passive"))
      (node (ref "C6-15") (pin "C") (pinfunction "C_C") (pintype "passive"))
      (node (ref "C6-9") (pin "C") (pinfunction "C_C") (pintype "passive"))
      (node (ref "C7-14") (pin "A") (pinfunction "A_A") (pintype "passive"))
      (node (ref "C8-14") (pin "A") (pinfunction "A_A") (pintype "passive"))
      (node (ref "U1") (pin "12") (pinfunction "CB6_12") (pintype "bidirectional"))
    )
    (net (code "17") (name "/CB7") (class "Default")
      (node (ref "C2-14") (pin "A") (pinfunction "A_A") (pintype "passive"))
      (node (ref "C3-14") (pin "A") (pinfunction "A_A") (pintype "passive"))
      (node (ref "C4-14") (pin "A") (pinfunction "A_A") (pintype "passive"))
      (node (ref "C5-14") (pin "A") (pinfunction "A_A") (pintype "passive"))
      (node (ref "C6-14") (pin "A") (pinfunction "A_A") (pintype "passive"))
      (node (ref "C7-10") (pin "C") (pinfunction "C_C") (pintype "passive"))
      (node (ref "C7-11") (pin "C") (pinfunction "C_C") (pintype "passive"))
      (node (ref "C7-12") (pin "C") (pinfunction "C_C") (pintype "passive"))
      (node (ref "C7-13") (pin "C") (pinfunction "C_C") (pintype "passive"))
      (node (ref "C7-14") (pin "C") (pinfunction "C_C") (pintype "passive"))
      (node (ref "C7-15") (pin "C") (pinfunction "C_C") (pintype "passive"))
      (node (ref "C7-9") (pin "C") (pinfunction "C_C") (pintype "passive"))
      (node (ref "C8-15") (pin "A") (pinfunction "A_A") (pintype "passive"))
      (node (ref "U1") (pin "13") (pinfunction "CB7_13") (pintype "bidirectional"))
    )
    (net (code "18") (name "/CB8") (class "Default")
      (node (ref "C2-15") (pin "A") (pinfunction "A_A") (pintype "passive"))
      (node (ref "C3-15") (pin "A") (pinfunction "A_A") (pintype "passive"))
      (node (ref "C4-15") (pin "A") (pinfunction "A_A") (pintype "passive"))
      (node (ref "C5-15") (pin "A") (pinfunction "A_A") (pintype "passive"))
      (node (ref "C6-15") (pin "A") (pinfunction "A_A") (pintype "passive"))
      (node (ref "C7-15") (pin "A") (pinfunction "A_A") (pintype "passive"))
      (node (ref "C8-10") (pin "C") (pinfunction "C_C") (pintype "passive"))
      (node (ref "C8-11") (pin "C") (pinfunction "C_C") (pintype "passive"))
      (node (ref "C8-12") (pin "C") (pinfunction "C_C") (pintype "passive"))
      (node (ref "C8-13") (pin "C") (pinfunction "C_C") (pintype "passive"))
      (node (ref "C8-14") (pin "C") (pinfunction "C_C") (pintype "passive"))
      (node (ref "C8-15") (pin "C") (pinfunction "C_C") (pintype "passive"))
      (node (ref "C8-9") (pin "C") (pinfunction "C_C") (pintype "passive"))
      (node (ref "U1") (pin "14") (pinfunction "CB8_14") (pintype "bidirectional"))
    )
    (net (code "19") (name "/DISPLAY_POWER") (class "Default")
      (node (ref "C2") (pin "1") (pinfunction "1_1") (pintype "passive"))
      (node (ref "C3") (pin "1") (pinfunction "1_1") (pintype "passive"))
      (node (ref "C7") (pin "1") (pinfunction "1_1") (pintype "passive"))
      (node (ref "J2") (pin "2") (pinfunction "2_2") (pintype "power_in"))
      (node (ref "R3") (pin "1") (pinfunction "1_1") (pintype "passive"))
      (node (ref "R4") (pin "2") (pinfunction "2_2") (pintype "passive"))
      (node (ref "U1") (pin "2") (pinfunction "VCC_2") (pintype "power_in"))
    )
    (net (code "20") (name "GND") (class "Default")
      (node (ref "C1") (pin "2") (pinfunction "2_2") (pintype "passive"))
      (node (ref "C2") (pin "2") (pinfunction "2_2") (pintype "passive"))
      (node (ref "C3") (pin "2") (pinfunction "2_2") (pintype "passive"))
      (node (ref "C7") (pin "2") (pinfunction "2_2") (pintype "passive"))
      (node (ref "J2") (pin "1") (pinfunction "1_1") (pintype "power_in"))
      (node (ref "R1") (pin "2") (pinfunction "2_2") (pintype "passive"))
      (node (ref "R2") (pin "2") (pinfunction "2_2") (pintype "passive"))
      (node (ref "U1") (pin "5") (pinfunction "GND_5") (pintype "power_in"))
      (node (ref "U1") (pin "THERMAL") (pinfunction "GND_THERMAL") (pintype "power_in"))
    )
    (net (code "21") (name "Net-(U1-C_FILT)") (class "Default")
      (node (ref "C1") (pin "1") (pinfunction "1_1") (pintype "passive"))
      (node (ref "U1") (pin "16") (pinfunction "C_FILT_16") (pintype "bidirectional"))
    )
    (net (code "22") (name "Net-(U1-INTB)") (class "Default")
      (node (ref "R4") (pin "1") (pinfunction "1_1") (pintype "passive"))
      (node (ref "U1") (pin "4") (pinfunction "INTB_4") (pintype "output"))
    )
    (net (code "23") (name "Net-(U1-R_EXT)") (class "Default")
      (node (ref "R2") (pin "1") (pinfunction "1_1") (pintype "passive"))
      (node (ref "U1") (pin "6") (pinfunction "R_EXT_6") (pintype "bidirectional"))
    )
    (net (code "24") (name "Net-(U1-SHUTDOWN)") (class "Default")
      (node (ref "R3") (pin "2") (pinfunction "2_2") (pintype "passive"))
      (node (ref "U1") (pin "3") (pinfunction "SHUTDOWN_3") (pintype "input"))
    )
    (net (code "25") (name "SCL") (class "Default")
      (node (ref "J2") (pin "4") (pinfunction "4_4") (pintype "passive"))
      (node (ref "U1") (pin "20") (pinfunction "SCL_20") (pintype "bidirectional"))
    )
    (net (code "26") (name "SDA") (class "Default")
      (node (ref "J2") (pin "3") (pinfunction "3_3") (pintype "passive"))
      (node (ref "U1") (pin "19") (pinfunction "SDA_19") (pintype "bidirectional"))
    )
    (net (code "27") (name "unconnected-(U1-AUDIOIN-Pad17)") (class "Default")
      (node (ref "U1") (pin "17") (pinfunction "AUDIOIN_17") (pintype "input"))
    )
    (net (code "28") (name "unconnected-(U1-CB9-Pad15)") (class "Default")
      (node (ref "U1") (pin "15") (pinfunction "CB9_15") (pintype "bidirectional"))
    )
  )
)
